# I2C_Bus_Multiplexer.net
KiCad netlist of a schematic drawn in Altium Designer
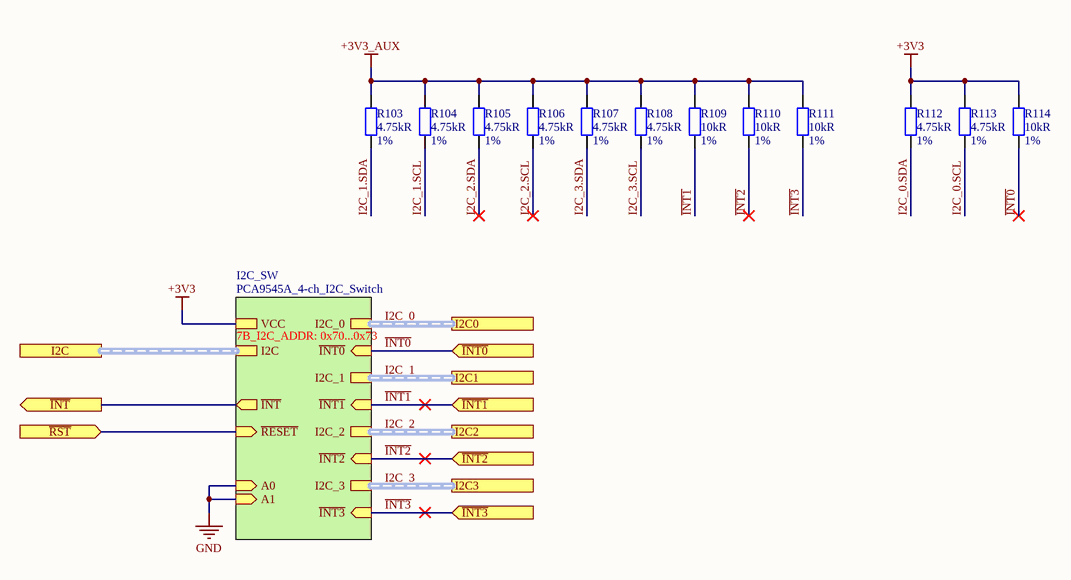
[diagram p0: I2C_Bus_Multiplexer.SchDoc]

(export (version "E")
  (design (tool "Eeschema 10.0.6"))
  (components
    (comp (ref "R103")
      (value "RES SMD 4.75K OHM 1% 1/16W 0402")
      (footprint "R0402")
      (description "4.75 kOhms ±1% 0.063W, 1/16W Chip Resistor 0402 (1005 Metric) Moisture Resistant Thick Film")
      (fields
        (field (name "MANUFACTURER") "Yageo")
        (field (name "MANUFACTURER PART NUMBER") "RC0402FR-074K75P")
        (field (name "RESISTANCE") "4.75kR")
        (field (name "TOLERANCE") "1%")
      )
      (libsource (lib "resistors_smd") (part "RES SMD 4.75K OHM 1% 1/16W 0402"))
    )
    (comp (ref "R104")
      (value "RES SMD 4.75K OHM 1% 1/16W 0402")
      (footprint "R0402")
      (description "4.75 kOhms ±1% 0.063W, 1/16W Chip Resistor 0402 (1005 Metric) Moisture Resistant Thick Film")
      (fields
        (field (name "MANUFACTURER") "Yageo")
        (field (name "MANUFACTURER PART NUMBER") "RC0402FR-074K75P")
        (field (name "RESISTANCE") "4.75kR")
        (field (name "TOLERANCE") "1%")
      )
      (libsource (lib "resistors_smd") (part "RES SMD 4.75K OHM 1% 1/16W 0402"))
    )
    (comp (ref "R105")
      (value "RES SMD 4.75K OHM 1% 1/16W 0402")
      (footprint "R0402")
      (description "4.75 kOhms ±1% 0.063W, 1/16W Chip Resistor 0402 (1005 Metric) Moisture Resistant Thick Film")
      (fields
        (field (name "MANUFACTURER") "Yageo")
        (field (name "MANUFACTURER PART NUMBER") "RC0402FR-074K75P")
        (field (name "RESISTANCE") "4.75kR")
        (field (name "TOLERANCE") "1%")
      )
      (libsource (lib "resistors_smd") (part "RES SMD 4.75K OHM 1% 1/16W 0402"))
    )
    (comp (ref "R106")
      (value "RES SMD 4.75K OHM 1% 1/16W 0402")
      (footprint "R0402")
      (description "4.75 kOhms ±1% 0.063W, 1/16W Chip Resistor 0402 (1005 Metric) Moisture Resistant Thick Film")
      (fields
        (field (name "MANUFACTURER") "Yageo")
        (field (name "MANUFACTURER PART NUMBER") "RC0402FR-074K75P")
        (field (name "RESISTANCE") "4.75kR")
        (field (name "TOLERANCE") "1%")
      )
      (libsource (lib "resistors_smd") (part "RES SMD 4.75K OHM 1% 1/16W 0402"))
    )
    (comp (ref "R107")
      (value "RES SMD 4.75K OHM 1% 1/16W 0402")
      (footprint "R0402")
      (description "4.75 kOhms ±1% 0.063W, 1/16W Chip Resistor 0402 (1005 Metric) Moisture Resistant Thick Film")
      (fields
        (field (name "MANUFACTURER") "Yageo")
        (field (name "MANUFACTURER PART NUMBER") "RC0402FR-074K75P")
        (field (name "RESISTANCE") "4.75kR")
        (field (name "TOLERANCE") "1%")
      )
      (libsource (lib "resistors_smd") (part "RES SMD 4.75K OHM 1% 1/16W 0402"))
    )
    (comp (ref "R108")
      (value "RES SMD 4.75K OHM 1% 1/16W 0402")
      (footprint "R0402")
      (description "4.75 kOhms ±1% 0.063W, 1/16W Chip Resistor 0402 (1005 Metric) Moisture Resistant Thick Film")
      (fields
        (field (name "MANUFACTURER") "Yageo")
        (field (name "MANUFACTURER PART NUMBER") "RC0402FR-074K75P")
        (field (name "RESISTANCE") "4.75kR")
        (field (name "TOLERANCE") "1%")
      )
      (libsource (lib "resistors_smd") (part "RES SMD 4.75K OHM 1% 1/16W 0402"))
    )
    (comp (ref "R109")
      (value "RES SMD 10K OHM 1% 1/16W 0402")
      (footprint "R0402")
      (description "10 kOhms ±1% 0.063W, 1/16W Chip Resistor 0402 (1005 Metric) Moisture Resistant Thick Film")
      (fields
        (field (name "MANUFACTURER") "Yageo")
        (field (name "MANUFACTURER PART NUMBER") "RC0402FR-0710KP")
        (field (name "RESISTANCE") "10kR")
        (field (name "TOLERANCE") "1%")
      )
      (libsource (lib "resistors_smd") (part "RES SMD 10K OHM 1% 1/16W 0402"))
    )
    (comp (ref "R110")
      (value "RES SMD 10K OHM 1% 1/16W 0402")
      (footprint "R0402")
      (description "10 kOhms ±1% 0.063W, 1/16W Chip Resistor 0402 (1005 Metric) Moisture Resistant Thick Film")
      (fields
        (field (name "MANUFACTURER") "Yageo")
        (field (name "MANUFACTURER PART NUMBER") "RC0402FR-0710KP")
        (field (name "RESISTANCE") "10kR")
        (field (name "TOLERANCE") "1%")
      )
      (libsource (lib "resistors_smd") (part "RES SMD 10K OHM 1% 1/16W 0402"))
    )
    (comp (ref "R111")
      (value "RES SMD 10K OHM 1% 1/16W 0402")
      (footprint "R0402")
      (description "10 kOhms ±1% 0.063W, 1/16W Chip Resistor 0402 (1005 Metric) Moisture Resistant Thick Film")
      (fields
        (field (name "MANUFACTURER") "Yageo")
        (field (name "MANUFACTURER PART NUMBER") "RC0402FR-0710KP")
        (field (name "RESISTANCE") "10kR")
        (field (name "TOLERANCE") "1%")
      )
      (libsource (lib "resistors_smd") (part "RES SMD 10K OHM 1% 1/16W 0402"))
    )
    (comp (ref "R112")
      (value "RES SMD 4.75K OHM 1% 1/16W 0402")
      (footprint "R0402")
      (description "4.75 kOhms ±1% 0.063W, 1/16W Chip Resistor 0402 (1005 Metric) Moisture Resistant Thick Film")
      (fields
        (field (name "MANUFACTURER") "Yageo")
        (field (name "MANUFACTURER PART NUMBER") "RC0402FR-074K75P")
        (field (name "RESISTANCE") "4.75kR")
        (field (name "TOLERANCE") "1%")
      )
      (libsource (lib "resistors_smd") (part "RES SMD 4.75K OHM 1% 1/16W 0402"))
    )
    (comp (ref "R113")
      (value "RES SMD 4.75K OHM 1% 1/16W 0402")
      (footprint "R0402")
      (description "4.75 kOhms ±1% 0.063W, 1/16W Chip Resistor 0402 (1005 Metric) Moisture Resistant Thick Film")
      (fields
        (field (name "MANUFACTURER") "Yageo")
        (field (name "MANUFACTURER PART NUMBER") "RC0402FR-074K75P")
        (field (name "RESISTANCE") "4.75kR")
        (field (name "TOLERANCE") "1%")
      )
      (libsource (lib "resistors_smd") (part "RES SMD 4.75K OHM 1% 1/16W 0402"))
    )
    (comp (ref "R114")
      (value "RES SMD 10K OHM 1% 1/16W 0402")
      (footprint "R0402")
      (description "10 kOhms ±1% 0.063W, 1/16W Chip Resistor 0402 (1005 Metric) Moisture Resistant Thick Film")
      (fields
        (field (name "MANUFACTURER") "Yageo")
        (field (name "MANUFACTURER PART NUMBER") "RC0402FR-0710KP")
        (field (name "RESISTANCE") "10kR")
        (field (name "TOLERANCE") "1%")
      )
      (libsource (lib "resistors_smd") (part "RES SMD 10K OHM 1% 1/16W 0402"))
    )
  )
  (nets
    (net (code "6") (name "+3V3") (class "Default")
      (node (ref "R112") (pin "2") (pinfunction "2_2") (pintype "passive"))
      (node (ref "R113") (pin "2") (pinfunction "2_2") (pintype "passive"))
      (node (ref "R114") (pin "1") (pinfunction "1_1") (pintype "passive"))
    )
    (net (code "7") (name "+3V3_AUX") (class "Default")
      (node (ref "R103") (pin "2") (pinfunction "2_2") (pintype "passive"))
      (node (ref "R104") (pin "2") (pinfunction "2_2") (pintype "passive"))
      (node (ref "R105") (pin "2") (pinfunction "2_2") (pintype "passive"))
      (node (ref "R106") (pin "2") (pinfunction "2_2") (pintype "passive"))
      (node (ref "R107") (pin "2") (pinfunction "2_2") (pintype "passive"))
      (node (ref "R108") (pin "2") (pinfunction "2_2") (pintype "passive"))
      (node (ref "R109") (pin "1") (pinfunction "1_1") (pintype "passive"))
      (node (ref "R110") (pin "1") (pinfunction "1_1") (pintype "passive"))
      (node (ref "R111") (pin "1") (pinfunction "1_1") (pintype "passive"))
    )
    (net (code "8") (name "/I2C_0.SCL") (class "Default")
      (node (ref "R113") (pin "1") (pinfunction "1_1") (pintype "passive"))
    )
    (net (code "9") (name "/I2C_0.SDA") (class "Default")
      (node (ref "R112") (pin "1") (pinfunction "1_1") (pintype "passive"))
    )
    (net (code "10") (name "/I2C_1.SCL") (class "Default")
      (node (ref "R104") (pin "1") (pinfunction "1_1") (pintype "passive"))
    )
    (net (code "11") (name "/I2C_1.SDA") (class "Default")
      (node (ref "R103") (pin "1") (pinfunction "1_1") (pintype "passive"))
    )
    (net (code "12") (name "/I2C_2.SCL") (class "Default")
      (node (ref "R106") (pin "1") (pinfunction "1_1") (pintype "passive+no_connect"))
    )
    (net (code "13") (name "/I2C_2.SDA") (class "Default")
      (node (ref "R105") (pin "1") (pinfunction "1_1") (pintype "passive+no_connect"))
    )
    (net (code "14") (name "/I2C_3.SCL") (class "Default")
      (node (ref "R108") (pin "1") (pinfunction "1_1") (pintype "passive"))
    )
    (net (code "15") (name "/I2C_3.SDA") (class "Default")
      (node (ref "R107") (pin "1") (pinfunction "1_1") (pintype "passive"))
    )
    (net (code "18") (name "/INT0") (class "Default")
      (node (ref "R114") (pin "2") (pinfunction "2_2") (pintype "passive"))
    )
    (net (code "19") (name "/INT1") (class "Default")
      (node (ref "R109") (pin "2") (pinfunction "2_2") (pintype "passive"))
    )
    (net (code "20") (name "/INT2") (class "Default")
      (node (ref "R110") (pin "2") (pinfunction "2_2") (pintype "passive"))
    )
    (net (code "21") (name "/INT3") (class "Default")
      (node (ref "R111") (pin "2") (pinfunction "2_2") (pintype "passive"))
    )
  )
)
